# vbus.net
KiCad netlist of a schematic drawn in EAGLE
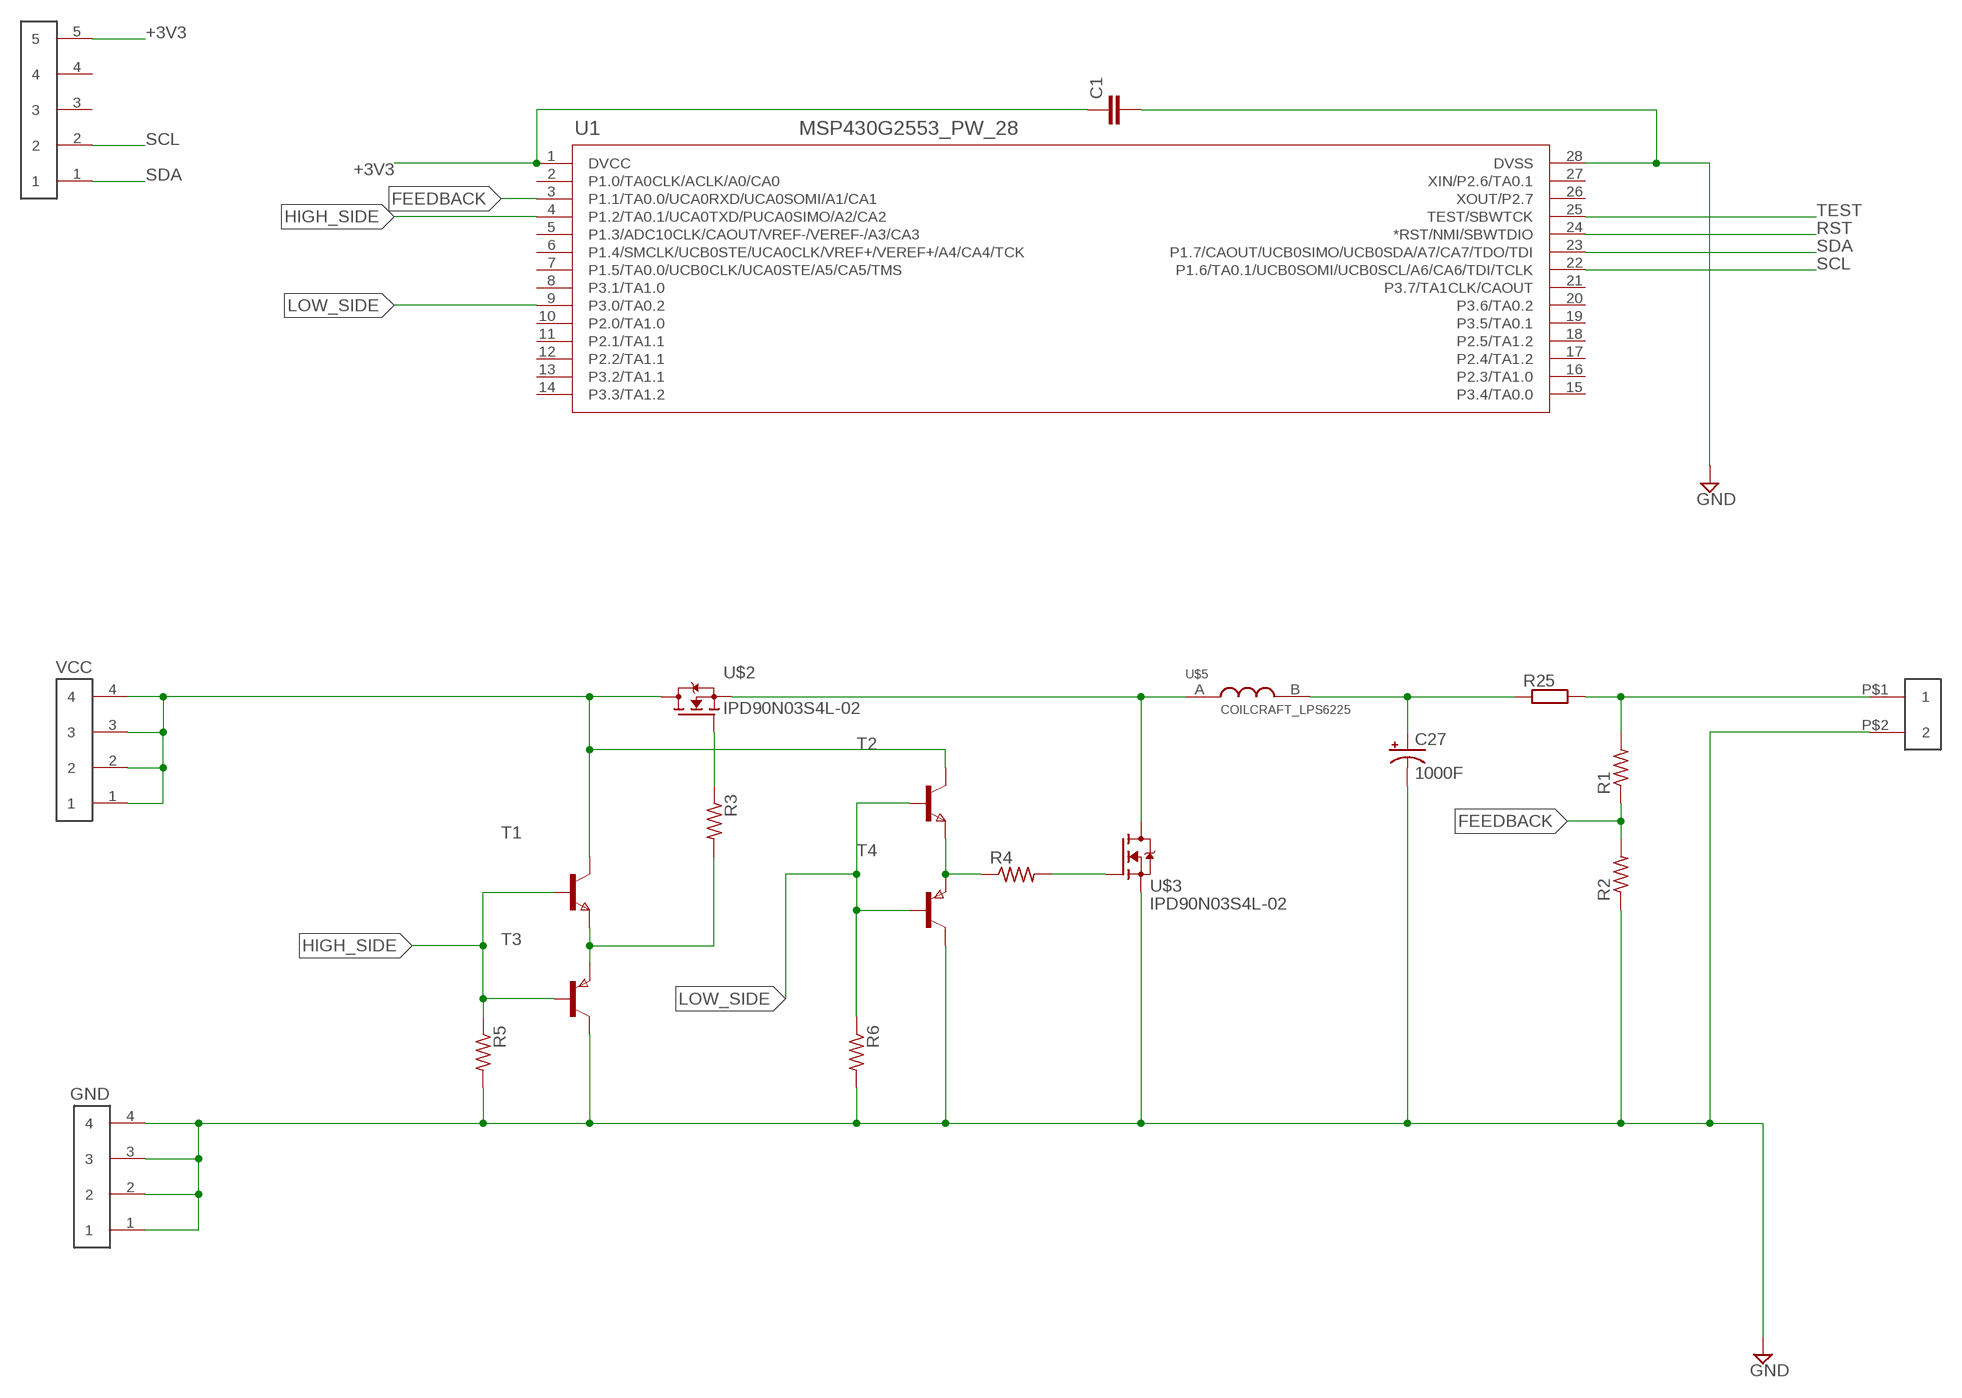
[diagram p0: schematic, sheet 1]

(export (version "E")
  (design (tool "Eeschema 10.0.6"))
  (components
    (comp (ref "C1")
      (value "C-EUC0603")
      (footprint "eagle-import:C0603")
      (libsource (lib "eagle-import") (part "C-EUC0603"))
    )
    (comp (ref "C27")
      (value "1000F")
      (footprint "eagle-import:TAP5-60")
      (libsource (lib "eagle-import") (part "CPOL-USTAP5-60"))
    )
    (comp (ref "R1")
      (value "R-US_R1206")
      (footprint "eagle-import:R1206")
      (libsource (lib "eagle-import") (part "R-US_R1206"))
    )
    (comp (ref "R2")
      (value "R-US_R1206")
      (footprint "eagle-import:R1206")
      (libsource (lib "eagle-import") (part "R-US_R1206"))
    )
    (comp (ref "R3")
      (value "R-US_R1206")
      (footprint "eagle-import:R1206")
      (libsource (lib "eagle-import") (part "R-US_R1206"))
    )
    (comp (ref "R4")
      (value "R-US_R1206")
      (footprint "eagle-import:R1206")
      (libsource (lib "eagle-import") (part "R-US_R1206"))
    )
    (comp (ref "R5")
      (value "R-US_R1206")
      (footprint "eagle-import:R1206")
      (libsource (lib "eagle-import") (part "R-US_R1206"))
    )
    (comp (ref "R6")
      (value "R-US_R1206")
      (footprint "eagle-import:R1206")
      (libsource (lib "eagle-import") (part "R-US_R1206"))
    )
    (comp (ref "R25")
      (value "SMR")
      (footprint "eagle-import:SMR")
      (libsource (lib "eagle-import") (part "SMR"))
    )
    (comp (ref "T1")
      (value "NPNSOT23-6")
      (footprint "eagle-import:SOT23-6")
      (fields (field (name "MPN") "ZXT13N50DE6"))
      (libsource (lib "eagle-import") (part "NPNSOT23-6"))
    )
    (comp (ref "T2")
      (value "NPNSOT23-6")
      (footprint "eagle-import:SOT23-6")
      (fields (field (name "MPN") "ZXT13N50DE6"))
      (libsource (lib "eagle-import") (part "NPNSOT23-6"))
    )
    (comp (ref "T3")
      (value "PNPSOT23-6")
      (footprint "eagle-import:SOT23-6")
      (fields (field (name "MPN") "ZXT13P12DE6"))
      (libsource (lib "eagle-import") (part "PNPSOT23-6"))
    )
    (comp (ref "T4")
      (value "PNPSOT23-6")
      (footprint "eagle-import:SOT23-6")
      (fields (field (name "MPN") "ZXT13P12DE6"))
      (libsource (lib "eagle-import") (part "PNPSOT23-6"))
    )
    (comp (ref "U$2")
      (value "IPD90N03S4L-02")
      (footprint "eagle-import:P_PG-TO252-3-11")
      (libsource (lib "eagle-import") (part "IPD90N03S4L-02"))
    )
    (comp (ref "U$3")
      (value "IPD90N03S4L-02")
      (footprint "eagle-import:P_PG-TO252-3-11")
      (libsource (lib "eagle-import") (part "IPD90N03S4L-02"))
    )
    (comp (ref "U$4")
      (value "1X5_HEADER")
      (footprint "eagle-import:1X5-.1HEADER")
      (libsource (lib "eagle-import") (part "1X5_HEADER"))
    )
    (comp (ref "U$5")
      (value "COILCRAFT_LPS6225")
      (footprint "eagle-import:INDUCTOR")
      (libsource (lib "eagle-import") (part "COILCRAFT_LPS6225"))
    )
    (comp (ref "U$11")
      (value "1X4_HEADER")
      (footprint "eagle-import:1X4-.1HEADER")
      (libsource (lib "eagle-import") (part "1X4_HEADER"))
    )
    (comp (ref "U$12")
      (value "1X4_HEADER")
      (footprint "eagle-import:1X4-.1HEADER")
      (libsource (lib "eagle-import") (part "1X4_HEADER"))
    )
    (comp (ref "U1")
      (value "MSP430G2553_PW_28")
      (footprint "eagle-import:PW28")
      (fields
        (field (name "GENERIC_PART_NUMBER") "MSP430G2553")
        (field (name "MANUFACTURER") "Texas Instruments")
        (field (name "MANUFACTURER_PART_NUMBER") "msp430g2553_pw_28")
      )
      (libsource (lib "eagle-import") (part "MSP430G2553_PW_28"))
    )
    (comp (ref "VBUS")
      (value "MOLEX-0436500200")
      (footprint "eagle-import:MOLEX_MICROFIT-2")
      (libsource (lib "eagle-import") (part "MOLEX-0436500200"))
    )
  )
  (nets
    (net (code "1") (name "/+3V3") (class "Default")
      (node (ref "C1") (pin "1") (pinfunction "1_1") (pintype "passive"))
      (node (ref "U$4") (pin "5") (pinfunction "5_5") (pintype "bidirectional"))
      (node (ref "U1") (pin "1") (pinfunction "DVCC_1") (pintype "power_in"))
    )
    (net (code "2") (name "/RST") (class "Default")
      (node (ref "U1") (pin "24") (pinfunction "*RST/NMI/SBWTDIO_24") (pintype "bidirectional"))
    )
    (net (code "3") (name "/SCL") (class "Default")
      (node (ref "U$4") (pin "2") (pinfunction "2_2") (pintype "bidirectional"))
      (node (ref "U1") (pin "22") (pinfunction "P1.6/TA0.1/UCB0SOMI/UCB0SCL/A6/CA6/TDI/TCLK_22") (pintype "bidirectional"))
    )
    (net (code "4") (name "/SDA") (class "Default")
      (node (ref "U$4") (pin "1") (pinfunction "1_1") (pintype "bidirectional"))
      (node (ref "U1") (pin "23") (pinfunction "P1.7/CAOUT/UCB0SIMO/UCB0SDA/A7/CA7/TDO/TDI_23") (pintype "bidirectional"))
    )
    (net (code "5") (name "/TEST") (class "Default")
      (node (ref "U1") (pin "25") (pinfunction "TEST/SBWTCK_25") (pintype "bidirectional"))
    )
    (net (code "6") (name "/VCC") (class "Default")
      (node (ref "T1") (pin "1") (pinfunction "C_1") (pintype "passive"))
      (node (ref "T1") (pin "2") (pinfunction "C_2") (pintype "passive"))
      (node (ref "T1") (pin "5") (pinfunction "C_5") (pintype "passive"))
      (node (ref "T1") (pin "6") (pinfunction "C_6") (pintype "passive"))
      (node (ref "T2") (pin "1") (pinfunction "C_1") (pintype "passive"))
      (node (ref "T2") (pin "2") (pinfunction "C_2") (pintype "passive"))
      (node (ref "T2") (pin "5") (pinfunction "C_5") (pintype "passive"))
      (node (ref "T2") (pin "6") (pinfunction "C_6") (pintype "passive"))
      (node (ref "U$11") (pin "1") (pinfunction "1_1") (pintype "bidirectional"))
      (node (ref "U$11") (pin "2") (pinfunction "2_2") (pintype "bidirectional"))
      (node (ref "U$11") (pin "3") (pinfunction "3_3") (pintype "bidirectional"))
      (node (ref "U$11") (pin "4") (pinfunction "4_4") (pintype "bidirectional"))
      (node (ref "U$2") (pin "2") (pinfunction "D_2") (pintype "passive"))
    )
    (net (code "7") (name "FEEDBACK") (class "Default")
      (node (ref "R1") (pin "1") (pinfunction "1_1") (pintype "passive"))
      (node (ref "R2") (pin "2") (pinfunction "2_2") (pintype "passive"))
      (node (ref "U1") (pin "3") (pinfunction "P1.1/TA0.0/UCA0RXD/UCA0SOMI/A1/CA1_3") (pintype "bidirectional"))
    )
    (net (code "8") (name "GND") (class "Default")
      (node (ref "C1") (pin "2") (pinfunction "2_2") (pintype "passive"))
      (node (ref "C27") (pin "-") (pinfunction "-_-") (pintype "passive"))
      (node (ref "R2") (pin "1") (pinfunction "1_1") (pintype "passive"))
      (node (ref "R5") (pin "2") (pinfunction "2_2") (pintype "passive"))
      (node (ref "R6") (pin "2") (pinfunction "2_2") (pintype "passive"))
      (node (ref "T3") (pin "1") (pinfunction "C_1") (pintype "passive"))
      (node (ref "T3") (pin "2") (pinfunction "C_2") (pintype "passive"))
      (node (ref "T3") (pin "5") (pinfunction "C_5") (pintype "passive"))
      (node (ref "T3") (pin "6") (pinfunction "C_6") (pintype "passive"))
      (node (ref "T4") (pin "1") (pinfunction "C_1") (pintype "passive"))
      (node (ref "T4") (pin "2") (pinfunction "C_2") (pintype "passive"))
      (node (ref "T4") (pin "5") (pinfunction "C_5") (pintype "passive"))
      (node (ref "T4") (pin "6") (pinfunction "C_6") (pintype "passive"))
      (node (ref "U$12") (pin "1") (pinfunction "1_1") (pintype "bidirectional"))
      (node (ref "U$12") (pin "2") (pinfunction "2_2") (pintype "bidirectional"))
      (node (ref "U$12") (pin "3") (pinfunction "3_3") (pintype "bidirectional"))
      (node (ref "U$12") (pin "4") (pinfunction "4_4") (pintype "bidirectional"))
      (node (ref "U$3") (pin "3") (pinfunction "S_3") (pintype "passive"))
      (node (ref "U1") (pin "28") (pinfunction "DVSS_28") (pintype "power_in"))
      (node (ref "VBUS") (pin "P$2") (pinfunction "2_P$2") (pintype "bidirectional"))
    )
    (net (code "9") (name "HIGH_SIDE") (class "Default")
      (node (ref "R5") (pin "1") (pinfunction "1_1") (pintype "passive"))
      (node (ref "T1") (pin "3") (pinfunction "B_3") (pintype "passive"))
      (node (ref "T3") (pin "3") (pinfunction "B_3") (pintype "passive"))
      (node (ref "U1") (pin "4") (pinfunction "P1.2/TA0.1/UCA0TXD/PUCA0SIMO/A2/CA2_4") (pintype "bidirectional"))
    )
    (net (code "10") (name "LOW_SIDE") (class "Default")
      (node (ref "R6") (pin "1") (pinfunction "1_1") (pintype "passive"))
      (node (ref "T2") (pin "3") (pinfunction "B_3") (pintype "passive"))
      (node (ref "T4") (pin "3") (pinfunction "B_3") (pintype "passive"))
      (node (ref "U1") (pin "9") (pinfunction "P3.0/TA0.2_9") (pintype "bidirectional"))
    )
    (net (code "11") (name "Net-(C27-Pad+)") (class "Default")
      (node (ref "C27") (pin "+") (pinfunction "+_+") (pintype "passive"))
      (node (ref "R25") (pin "2") (pinfunction "2_2") (pintype "passive"))
      (node (ref "U$5") (pin "B") (pinfunction "B_B") (pintype "bidirectional"))
    )
    (net (code "12") (name "Net-(T1-E)") (class "Default")
      (node (ref "R3") (pin "2") (pinfunction "2_2") (pintype "passive"))
      (node (ref "T1") (pin "4") (pinfunction "E_4") (pintype "passive"))
      (node (ref "T3") (pin "4") (pinfunction "E_4") (pintype "passive"))
    )
    (net (code "13") (name "Net-(T2-E)") (class "Default")
      (node (ref "R4") (pin "1") (pinfunction "1_1") (pintype "passive"))
      (node (ref "T2") (pin "4") (pinfunction "E_4") (pintype "passive"))
      (node (ref "T4") (pin "4") (pinfunction "E_4") (pintype "passive"))
    )
    (net (code "14") (name "Net-(U$2-G)") (class "Default")
      (node (ref "R3") (pin "1") (pinfunction "1_1") (pintype "passive"))
      (node (ref "U$2") (pin "1") (pinfunction "G_1") (pintype "passive"))
    )
    (net (code "15") (name "Net-(U$2-S)") (class "Default")
      (node (ref "U$2") (pin "3") (pinfunction "S_3") (pintype "passive"))
      (node (ref "U$3") (pin "2") (pinfunction "D_2") (pintype "passive"))
      (node (ref "U$5") (pin "A") (pinfunction "A_A") (pintype "bidirectional"))
    )
    (net (code "16") (name "Net-(U$3-G)") (class "Default")
      (node (ref "R4") (pin "2") (pinfunction "2_2") (pintype "passive"))
      (node (ref "U$3") (pin "1") (pinfunction "G_1") (pintype "passive"))
    )
    (net (code "17") (name "Net-(VBUS-1)") (class "Default")
      (node (ref "R1") (pin "2") (pinfunction "2_2") (pintype "passive"))
      (node (ref "R25") (pin "1") (pinfunction "1_1") (pintype "passive"))
      (node (ref "VBUS") (pin "P$1") (pinfunction "1_P$1") (pintype "bidirectional"))
    )
    (net (code "18") (name "unconnected-(U$4-Pad3)") (class "Default")
      (node (ref "U$4") (pin "3") (pinfunction "3_3") (pintype "bidirectional"))
    )
    (net (code "19") (name "unconnected-(U$4-Pad4)") (class "Default")
      (node (ref "U$4") (pin "4") (pinfunction "4_4") (pintype "bidirectional"))
    )
    (net (code "20") (name "unconnected-(U1-P1.0{slash}TA0CLK{slash}ACLK{slash}A0{slash}CA0-Pad2)") (class "Default")
      (node (ref "U1") (pin "2") (pinfunction "P1.0/TA0CLK/ACLK/A0/CA0_2") (pintype "bidirectional"))
    )
    (net (code "21") (name "unconnected-(U1-P1.3{slash}ADC10CLK{slash}CAOUT{slash}VREF-{slash}VEREF-{slash}A3{slash}CA3-Pad5)") (class "Default")
      (node (ref "U1") (pin "5") (pinfunction "P1.3/ADC10CLK/CAOUT/VREF-/VEREF-/A3/CA3_5") (pintype "bidirectional"))
    )
    (net (code "22") (name "unconnected-(U1-P1.4{slash}SMCLK{slash}UCB0STE{slash}UCA0CLK{slash}VREF+{slash}VEREF+{slash}A4{slash}CA4{slash}TCK-Pad6)") (class "Default")
      (node (ref "U1") (pin "6") (pinfunction "P1.4/SMCLK/UCB0STE/UCA0CLK/VREF+/VEREF+/A4/CA4/TCK_6") (pintype "bidirectional"))
    )
    (net (code "23") (name "unconnected-(U1-P1.5{slash}TA0.0{slash}UCB0CLK{slash}UCA0STE{slash}A5{slash}CA5{slash}TMS-Pad7)") (class "Default")
      (node (ref "U1") (pin "7") (pinfunction "P1.5/TA0.0/UCB0CLK/UCA0STE/A5/CA5/TMS_7") (pintype "bidirectional"))
    )
    (net (code "24") (name "unconnected-(U1-P2.0{slash}TA1.0-Pad10)") (class "Default")
      (node (ref "U1") (pin "10") (pinfunction "P2.0/TA1.0_10") (pintype "bidirectional"))
    )
    (net (code "25") (name "unconnected-(U1-P2.1{slash}TA1.1-Pad11)") (class "Default")
      (node (ref "U1") (pin "11") (pinfunction "P2.1/TA1.1_11") (pintype "bidirectional"))
    )
    (net (code "26") (name "unconnected-(U1-P2.2{slash}TA1.1-Pad12)") (class "Default")
      (node (ref "U1") (pin "12") (pinfunction "P2.2/TA1.1_12") (pintype "bidirectional"))
    )
    (net (code "27") (name "unconnected-(U1-P2.3{slash}TA1.0-Pad16)") (class "Default")
      (node (ref "U1") (pin "16") (pinfunction "P2.3/TA1.0_16") (pintype "bidirectional"))
    )
    (net (code "28") (name "unconnected-(U1-P2.4{slash}TA1.2-Pad17)") (class "Default")
      (node (ref "U1") (pin "17") (pinfunction "P2.4/TA1.2_17") (pintype "bidirectional"))
    )
    (net (code "29") (name "unconnected-(U1-P2.5{slash}TA1.2-Pad18)") (class "Default")
      (node (ref "U1") (pin "18") (pinfunction "P2.5/TA1.2_18") (pintype "bidirectional"))
    )
    (net (code "30") (name "unconnected-(U1-P3.1{slash}TA1.0-Pad8)") (class "Default")
      (node (ref "U1") (pin "8") (pinfunction "P3.1/TA1.0_8") (pintype "bidirectional"))
    )
    (net (code "31") (name "unconnected-(U1-P3.2{slash}TA1.1-Pad13)") (class "Default")
      (node (ref "U1") (pin "13") (pinfunction "P3.2/TA1.1_13") (pintype "bidirectional"))
    )
    (net (code "32") (name "unconnected-(U1-P3.3{slash}TA1.2-Pad14)") (class "Default")
      (node (ref "U1") (pin "14") (pinfunction "P3.3/TA1.2_14") (pintype "bidirectional"))
    )
    (net (code "33") (name "unconnected-(U1-P3.4{slash}TA0.0-Pad15)") (class "Default")
      (node (ref "U1") (pin "15") (pinfunction "P3.4/TA0.0_15") (pintype "bidirectional"))
    )
    (net (code "34") (name "unconnected-(U1-P3.5{slash}TA0.1-Pad19)") (class "Default")
      (node (ref "U1") (pin "19") (pinfunction "P3.5/TA0.1_19") (pintype "bidirectional"))
    )
    (net (code "35") (name "unconnected-(U1-P3.6{slash}TA0.2-Pad20)") (class "Default")
      (node (ref "U1") (pin "20") (pinfunction "P3.6/TA0.2_20") (pintype "bidirectional"))
    )
    (net (code "36") (name "unconnected-(U1-P3.7{slash}TA1CLK{slash}CAOUT-Pad21)") (class "Default")
      (node (ref "U1") (pin "21") (pinfunction "P3.7/TA1CLK/CAOUT_21") (pintype "bidirectional"))
    )
    (net (code "37") (name "unconnected-(U1-XIN{slash}P2.6{slash}TA0.1-Pad27)") (class "Default")
      (node (ref "U1") (pin "27") (pinfunction "XIN/P2.6/TA0.1_27") (pintype "bidirectional"))
    )
    (net (code "38") (name "unconnected-(U1-XOUT{slash}P2.7-Pad26)") (class "Default")
      (node (ref "U1") (pin "26") (pinfunction "XOUT/P2.7_26") (pintype "bidirectional"))
    )
  )
)
